# 4_Buck_Boost_12V.net
KiCad netlist of a schematic drawn in Altium Designer
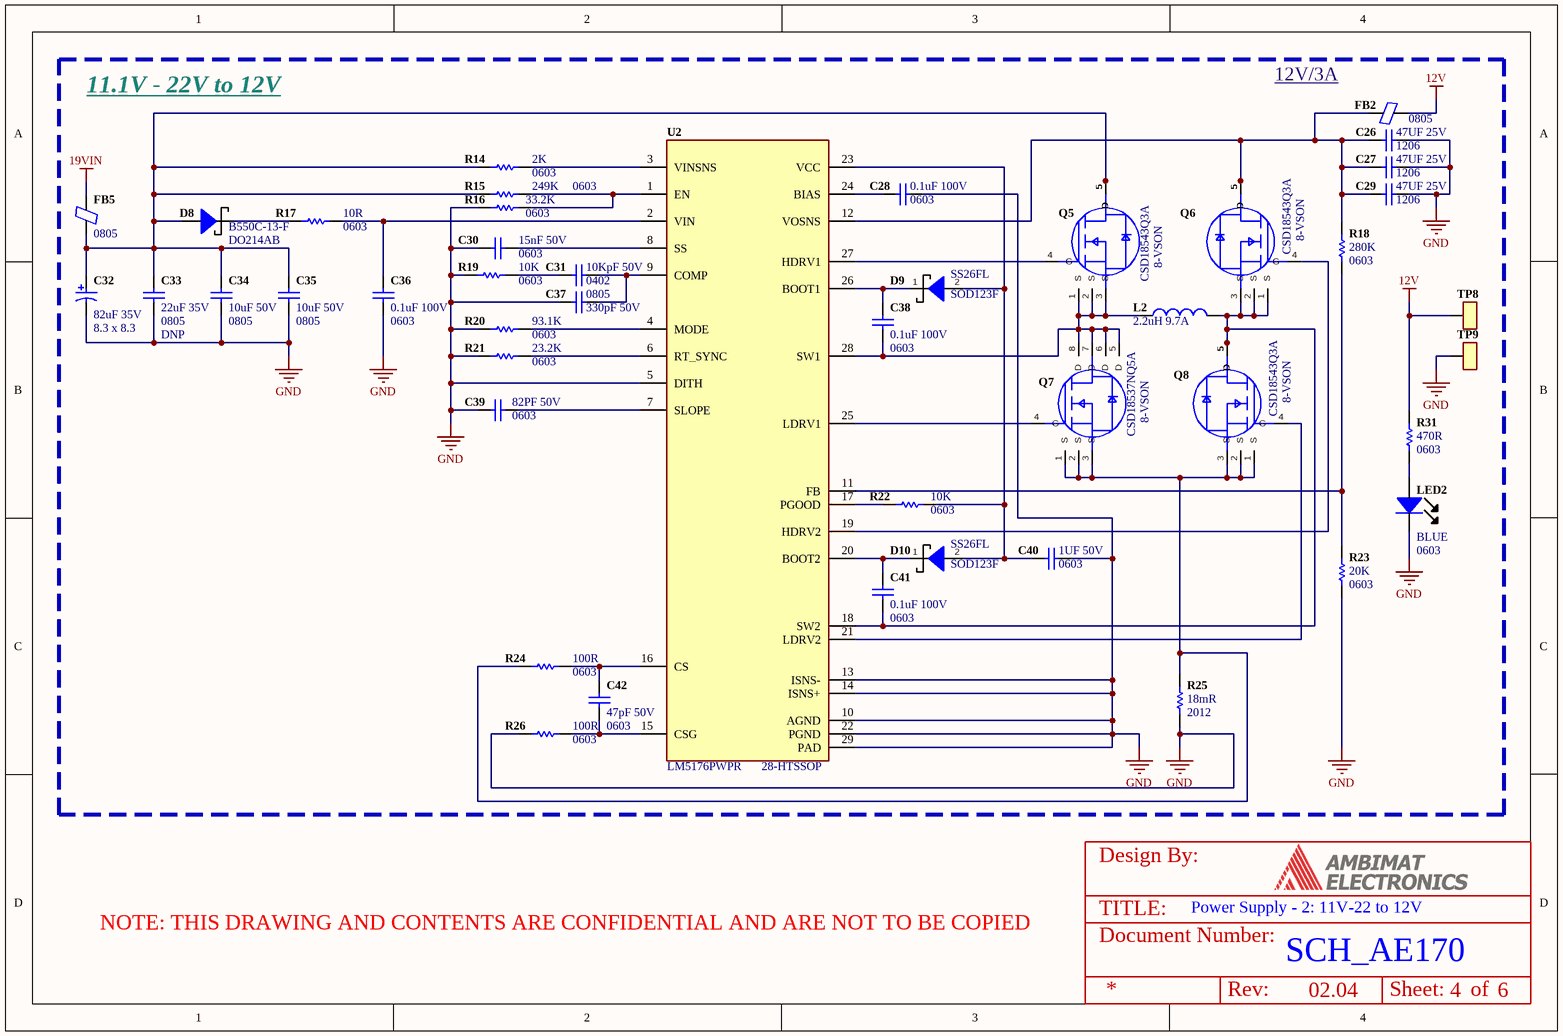
[diagram p0: 4. Buck Boost_12V.SchDoc]

(export (version "E")
  (design (tool "Eeschema 10.0.6"))
  (components
    (comp (ref "C26")
      (value "CAP CER 47UF 25V X5R 1206")
      (footprint "LimLabDL:1206 - NP")
      (fields
        (field (name "MANUFACTURER PART NUMBER") "C3216X5R1E476M160AC")
        (field (name "MANUFACTURER") "TDK Corporation")
        (field (name "VENDOR-1 PART NUMBER") "445-8047-1-ND")
        (field (name "PART NAME") "47UF 25V")
        (field (name "PCB FOOTPRINT") "1206")
      )
      (libsource (lib "LimLabDL") (part "CS47UF-25V1206"))
    )
    (comp (ref "C27")
      (value "CAP CER 47UF 25V X5R 1206")
      (footprint "LimLabDL:1206 - NP")
      (fields
        (field (name "MANUFACTURER PART NUMBER") "C3216X5R1E476M160AC")
        (field (name "MANUFACTURER") "TDK Corporation")
        (field (name "VENDOR-1 PART NUMBER") "445-8047-1-ND")
        (field (name "PART NAME") "47UF 25V")
        (field (name "PCB FOOTPRINT") "1206")
      )
      (libsource (lib "LimLabDL") (part "CS47UF-25V1206"))
    )
    (comp (ref "C28")
      (value "CAP CER 0.1UF 100V X7R 0603")
      (footprint "LimLabDL:0603C")
      (fields
        (field (name "MANU PART NUMBER") "CC0603KRX7R0BB104")
        (field (name "MANUFACTURER") "YAGEO")
        (field (name "PART NAME") "0.1uF 100V")
        (field (name "PCB FOOTPRINT") "0603")
        (field (name "VENDOR-1 PART NUMBER") "311-1523-1-ND")
      )
      (libsource (lib "LimLabDL") (part "CS0.1uF-100V0603"))
    )
    (comp (ref "C29")
      (value "CAP CER 47UF 25V X5R 1206")
      (footprint "LimLabDL:1206 - NP")
      (fields
        (field (name "MANUFACTURER PART NUMBER") "C3216X5R1E476M160AC")
        (field (name "MANUFACTURER") "TDK Corporation")
        (field (name "VENDOR-1 PART NUMBER") "445-8047-1-ND")
        (field (name "PART NAME") "47UF 25V")
        (field (name "PCB FOOTPRINT") "1206")
      )
      (libsource (lib "LimLabDL") (part "CS47UF-25V1206"))
    )
    (comp (ref "C30")
      (value "CAP CER 0.015UF 50V X7R 0603")
      (footprint "LimLabDL:0603C")
      (fields
        (field (name "MANUFACTURER PART NUMBER") "CL10B153KB8NNNC")
        (field (name "MANUFACTURER") "Samsung Electro-Mechanics")
        (field (name "VENDOR-1 PART NUMBER") "1276-1277-1-ND")
        (field (name "PART NAME") "15nF 50V")
        (field (name "PCB FOOTPRINT") "0603")
      )
      (libsource (lib "LimLabDL") (part "CS15nF-50V0603"))
    )
    (comp (ref "C31")
      (value "CAP CER 10000PF 50V X7R 0402")
      (footprint "LimLabDL:0402C")
      (fields
        (field (name "MANUFACTURER") "TDK Corporation")
        (field (name "VENDOR-1 PART NUMBER") "445-6893-1-ND")
        (field (name "PART NAME") "10KpF 50V")
        (field (name "PCB FOOTPRINT") "0402")
        (field (name "MANUFACTURER PART NUMBER") "CGA2B3X7R1H103K050BB")
      )
      (libsource (lib "LimLabDL") (part "CS10000pF-50V0402"))
    )
    (comp (ref "C32")
      (value "CAP ALUM POLY 82UF 20% 35V SMD")
      (footprint "LimLabDL:CAP_PC_8X12_NCH")
      (fields
        (field (name "MANU PART NUMBER") "35SVPF82M")
        (field (name "MANUFACTURER") "Panasonic")
        (field (name "VENDOR-1 PART NUMBER") "P16562CT-ND")
        (field (name "PART NAME") "82uF 35V")
        (field (name "PCB FOOTPRINT") "8.3 x 8.3")
      )
      (libsource (lib "LimLabDL") (part "CS82uF-35VALUM"))
    )
    (comp (ref "C33")
      (value "CAP CER 22UF 35V X5R 0805")
      (footprint "LimLabDL:0805C")
      (fields
        (field (name "MANU PART NUMBER") "C2012X5R1V226M125AC")
        (field (name "MANUFACTURER") "TDK Corporation")
        (field (name "MOUNTING") "DNP")
        (field (name "VENDOR-1 PART NUMBER") "445-14428-1-ND")
        (field (name "PART NAME") "22uF 35V")
        (field (name "PCB FOOTPRINT") "0805")
      )
      (libsource (lib "LimLabDL") (part "CS22uF-35V0805"))
    )
    (comp (ref "C34")
      (value "CAP CER 10UF 50V X5R 0805")
      (footprint "LimLabDL:0805C")
      (fields
        (field (name "MANU PART NUMBER") "GRM21BR61H106KE43L")
        (field (name "MANUFACTURER") "Murata Electronics")
        (field (name "VENDOR-1 PART NUMBER") "490-18663-1-ND")
        (field (name "PART NAME") "10uF 50V")
        (field (name "PCB FOOTPRINT") "0805")
      )
      (libsource (lib "LimLabDL") (part "CS10uF-50V0805"))
    )
    (comp (ref "C35")
      (value "CAP CER 10UF 50V X5R 0805")
      (footprint "LimLabDL:0805C")
      (fields
        (field (name "MANU PART NUMBER") "GRM21BR61H106KE43L")
        (field (name "MANUFACTURER") "Murata Electronics")
        (field (name "VENDOR-1 PART NUMBER") "490-18663-1-ND")
        (field (name "PART NAME") "10uF 50V")
        (field (name "PCB FOOTPRINT") "0805")
      )
      (libsource (lib "LimLabDL") (part "CS10uF-50V0805"))
    )
    (comp (ref "C36")
      (value "CAP CER 0.1UF 100V X7R 0603")
      (footprint "LimLabDL:0603C")
      (fields
        (field (name "MANU PART NUMBER") "CC0603KRX7R0BB104")
        (field (name "MANUFACTURER") "YAGEO")
        (field (name "PART NAME") "0.1uF 100V")
        (field (name "PCB FOOTPRINT") "0603")
        (field (name "VENDOR-1 PART NUMBER") "311-1523-1-ND")
      )
      (libsource (lib "LimLabDL") (part "CS0.1uF-100V0603"))
    )
    (comp (ref "C37")
      (value "CAP CER 330PF 50V C0G/NPO 0805")
      (footprint "LimLabDL:0805C")
      (fields
        (field (name "MANUFACTURER") "YAGEO")
        (field (name "VENDOR-1 PART NUMBER") "311-1117-1-ND")
        (field (name "PART NAME") "330pF 50V")
        (field (name "PCB FOOTPRINT") "0805")
        (field (name "MANUFACTURER PART NUMBER") "CC0805JRNPO9BN331")
      )
      (libsource (lib "LimLabDL") (part "CS330pF-50V0805"))
    )
    (comp (ref "C38")
      (value "CAP CER 0.1UF 100V X7R 0603")
      (footprint "LimLabDL:0603C")
      (fields
        (field (name "MANU PART NUMBER") "CC0603KRX7R0BB104")
        (field (name "MANUFACTURER") "YAGEO")
        (field (name "PART NAME") "0.1uF 100V")
        (field (name "PCB FOOTPRINT") "0603")
        (field (name "VENDOR-1 PART NUMBER") "311-1523-1-ND")
      )
      (libsource (lib "LimLabDL") (part "CS0.1uF-100V0603"))
    )
    (comp (ref "C39")
      (value "CAP CER 82PF 50V C0G/NPO 0603")
      (footprint "LimLabDL:0603C")
      (fields
        (field (name "MANUFACTURER") "Yageo")
        (field (name "VENDOR-1 PART NUMBER") "311-1068-1-ND")
        (field (name "PART NAME") "82PF 50V")
        (field (name "PCB FOOTPRINT") "0603")
        (field (name "MANU PART NUMBER") "CC0603JRNPO9BN820")
      )
      (libsource (lib "LimLabDL") (part "CS82pF-50V0603"))
    )
    (comp (ref "C40")
      (value "CAP CER 1UF 50V X7R 0603")
      (footprint "LimLabDL:0603C")
      (fields
        (field (name "MANU PART NUMBER") "CC0603KRX7R9BB105")
        (field (name "MANUFACTURER") "Yageo")
        (field (name "PART NAME") "1UF 50V")
        (field (name "PCB FOOTPRINT") "0603")
        (field (name "VENDOR-1 PART NUMBER") "311-2082-1-ND")
      )
      (libsource (lib "LimLabDL") (part "CS1uF-50V0603"))
    )
    (comp (ref "C41")
      (value "CAP CER 0.1UF 100V X7R 0603")
      (footprint "LimLabDL:0603C")
      (fields
        (field (name "MANU PART NUMBER") "CC0603KRX7R0BB104")
        (field (name "MANUFACTURER") "YAGEO")
        (field (name "PART NAME") "0.1uF 100V")
        (field (name "PCB FOOTPRINT") "0603")
        (field (name "VENDOR-1 PART NUMBER") "311-1523-1-ND")
      )
      (libsource (lib "LimLabDL") (part "CS0.1uF-100V0603"))
    )
    (comp (ref "C42")
      (value "CAP CER 47PF 50V X7R 10% 0603")
      (footprint "LimLabDL:0603C")
      (fields
        (field (name "MANUFACTURER") "KEMET")
        (field (name "VENDOR-1 PART NUMBER") "399-16402-1-ND")
        (field (name "PART NAME") "47pF 50V")
        (field (name "PCB FOOTPRINT") "0603")
        (field (name "MANUFACTURER PART NUMBER") "C0603C470K5RAC7867")
      )
      (libsource (lib "LimLabDL") (part "CS47pF-50V0603"))
    )
    (comp (ref "D8")
      (value "DIODE SCHOTTKY 50V 5A SMC")
      (footprint "LimLabDL:DO-214AB-SHKY")
      (fields
        (field (name "MANU PART NUMBER") "B550C-13-F")
        (field (name "MANUFACTURER") "Diodes Incorporated")
        (field (name "VENDOR-1 PART NUMBER") "B550C-FDICT-ND")
        (field (name "PCB FOOTPRINT") "DO214AB")
        (field (name "PART NAME") "B550C-13-F")
      )
      (libsource (lib "LimLabDL") (part "DS-B550C-13-F"))
    )
    (comp (ref "D9")
      (value "DIODE SCHOTTKY 60V 2A SOD123F")
      (footprint "LimLabDL:SOD123F-SHKY")
      (fields
        (field (name "MANU PART NUMBER") "SS26FL")
        (field (name "MANUFACTURER") "onsemi")
        (field (name "VENDOR-1 PART NUMBER") "SS26FLCT-ND")
        (field (name "PCB FOOTPRINT") "SOD123F")
        (field (name "PART NAME") "SS26FL")
      )
      (libsource (lib "LimLabDL") (part "DS-SS26FL"))
    )
    (comp (ref "D10")
      (value "DIODE SCHOTTKY 60V 2A SOD123F")
      (footprint "LimLabDL:SOD123F-SHKY")
      (fields
        (field (name "MANU PART NUMBER") "SS26FL")
        (field (name "MANUFACTURER") "onsemi")
        (field (name "VENDOR-1 PART NUMBER") "SS26FLCT-ND")
        (field (name "PCB FOOTPRINT") "SOD123F")
        (field (name "PART NAME") "SS26FL")
      )
      (libsource (lib "LimLabDL") (part "DS-SS26FL"))
    )
    (comp (ref "FB2")
      (value "FERRITE BEAD 120 OHM 0805 1LN")
      (footprint "LimLabDL:0805F")
      (fields
        (field (name "MANUFACTURER") "Pulse Electronics")
        (field (name "MANUFACTURER PART NUMBER") "ABUP00201209121Y00")
        (field (name "VENDOR-1 PART NUMBER") "553-ABUP00201209121Y00CT-ND")
        (field (name "PCB FOOTPRINT") "0805")
      )
      (libsource (lib "LimLabDL") (part "FB120OHM-0805"))
    )
    (comp (ref "FB5")
      (value "FERRITE BEAD 120 OHM 0805 1LN")
      (footprint "LimLabDL:0805F")
      (fields
        (field (name "MANUFACTURER") "Pulse Electronics")
        (field (name "MANUFACTURER PART NUMBER") "ABUP00201209121Y00")
        (field (name "VENDOR-1 PART NUMBER") "553-ABUP00201209121Y00CT-ND")
        (field (name "PCB FOOTPRINT") "0805")
      )
      (libsource (lib "LimLabDL") (part "FB120OHM-0805"))
    )
    (comp (ref "L2")
      (value "FIXED IND 2.2UH 9.7A 14.5MOHM SM")
      (footprint "LimLabDL:IND_BOURNS_SRP5030")
      (fields
        (field (name "MANUFACTURER PART NUMBER") "SRP5030CA-2R2M")
        (field (name "MANUFACTURER") "Bourns Inc.")
        (field (name "VENDOR-1 PART NUMBER") "SRP5030CA-2R2MCT-ND")
        (field (name "PART NAME") "2.2uH 9.7A")
      )
      (libsource (lib "LimLabDL") (part "LS2.2uH9.7A-5553"))
    )
    (comp (ref "LED2")
      (value "LB Q39G-L2N2-35-1")
      (footprint "LimLabDL:LED0603_BLUE")
      (description "LED BLUE CLEAR 3MM 470NM")
      (fields
        (field (name "MANUFACTURER") "OSRAM Opto Semiconductors Inc")
        (field (name "VENDOR-1 PART NUMBER") "475-2816-1-ND")
        (field (name "PCB FOOTPRINT") "0603")
        (field (name "COLOR") "BLUE")
      )
      (libsource (lib "LimLabDL") (part "LED-BLUE0603"))
    )
    (comp (ref "Q5")
      (value "MOSFET N-CH 60V 60A 8VSON")
      (footprint "LimLabDL:SON65P300X350X90-9N")
      (fields
        (field (name "MANU PART NUMBER") "CSD18543Q3A")
        (field (name "MANUFACTURER") "Texas Instruments")
        (field (name "VENDOR-1 PART NUMBER") "296-47321-1-ND")
        (field (name "PCB FOOTPRINT") "8-VSON")
        (field (name "PART NAME") "CSD18543Q3A")
      )
      (libsource (lib "LimLabDL") (part "MS-CSD18543Q3A"))
    )
    (comp (ref "Q6")
      (value "MOSFET N-CH 60V 60A 8VSON")
      (footprint "LimLabDL:SON65P300X350X90-9N")
      (fields
        (field (name "MANU PART NUMBER") "CSD18543Q3A")
        (field (name "MANUFACTURER") "Texas Instruments")
        (field (name "VENDOR-1 PART NUMBER") "296-47321-1-ND")
        (field (name "PCB FOOTPRINT") "8-VSON")
        (field (name "PART NAME") "CSD18543Q3A")
      )
      (libsource (lib "LimLabDL") (part "MS-CSD18543Q3A"))
    )
    (comp (ref "Q7")
      (value "MOSFET N-CH 60V 50A 8VSON")
      (footprint "LimLabDL:SON127P500X600")
      (fields
        (field (name "MANU PART NUMBER") "CSD18537NQ5A")
        (field (name "MANUFACTURER") "Texas Instruments")
        (field (name "VENDOR-1 PART NUMBER") "296-36455-1-ND")
        (field (name "PCB FOOTPRINT") "8-VSON")
        (field (name "PART NAME") "CSD18537NQ5A")
      )
      (libsource (lib "LimLabDL") (part "MS-CSD18537NQ5A"))
    )
    (comp (ref "Q8")
      (value "MOSFET N-CH 60V 60A 8VSON")
      (footprint "LimLabDL:SON65P300X350X90-9N")
      (fields
        (field (name "MANU PART NUMBER") "CSD18543Q3A")
        (field (name "MANUFACTURER") "Texas Instruments")
        (field (name "VENDOR-1 PART NUMBER") "296-47321-1-ND")
        (field (name "PCB FOOTPRINT") "8-VSON")
        (field (name "PART NAME") "CSD18543Q3A")
      )
      (libsource (lib "LimLabDL") (part "MS-CSD18543Q3A"))
    )
    (comp (ref "R14")
      (value "RS2K-0.1W0603")
      (footprint "LimLabDL:0603")
      (description "RES SMD 2K OHM 5% 1/10W 0603")
      (fields
        (field (name "MANU PART NUMBER") "ERJ-3GEYJ202V")
        (field (name "MANUFACTURER") "Panasonic")
        (field (name "PART NAME") "2K")
        (field (name "PCB FOOTPRINT") "0603")
      )
      (libsource (lib "LimLabDL") (part "RS2K-0.1W0603"))
    )
    (comp (ref "R15")
      (value "RES SMD 249K OHM 1% 1/10W 0603")
      (footprint "LimLabDL:0603")
      (fields
        (field (name "MANUFACTURER PART NUMBER") "AC0603FR-07249KL")
        (field (name "MANUFACTURER") "Yageo")
        (field (name "VENDOR-1 PART NUMBER") "13-AC0603FR-07249KLCT-ND")
        (field (name "PART NAME") "249K")
        (field (name "PCB FOOTPRINT") "0603")
      )
      (libsource (lib "LimLabDL") (part "RS249K-0.1W0603"))
    )
    (comp (ref "R16")
      (value "RES SMD 33.2K OHM 1% 1/10W 0603")
      (footprint "LimLabDL:0603")
      (fields
        (field (name "MANUFACTURER") "Panasonic Electronic Components")
        (field (name "VENDOR-1 PART NUMBER") "P33.2KHCT-ND")
        (field (name "PART NAME") "33.2K")
        (field (name "PCB FOOTPRINT") "0603")
        (field (name "MANU PART NUMBER") "ERJ-3EKF3322V")
      )
      (libsource (lib "LimLabDL") (part "RS33.2K-0.1W0603"))
    )
    (comp (ref "R17")
      (value "RES SMD 10 OHM 1% 1/10W 0603")
      (footprint "LimLabDL:0603")
      (fields
        (field (name "MANU PART NUMBER") "CRCW060310R0FKEA")
        (field (name "MANUFACTURER") "Vishay Dale")
        (field (name "VENDOR-1 PART NUMBER") "541-10.0HCT-ND")
        (field (name "PART NAME") "10R")
        (field (name "PCB FOOTPRINT") "0603")
      )
      (libsource (lib "LimLabDL") (part "RS10R-0.1W0603"))
    )
    (comp (ref "R18")
      (value "RES SMD 280K OHM 1% 1/10W 0603")
      (footprint "LimLabDL:0603")
      (fields
        (field (name "MANU PART NUMBER") "CRCW0603280KFKEA")
        (field (name "MANUFACTURER") "Vishay Dale")
        (field (name "VENDOR-1 PART NUMBER") "541-280KHCT-ND")
        (field (name "PART NAME") "280K")
        (field (name "PCB FOOTPRINT") "0603")
      )
      (libsource (lib "LimLabDL") (part "RS280K-0.1W0603"))
    )
    (comp (ref "R19")
      (value "RES SMD 10K OHM 5% 1/10W 0603")
      (footprint "LimLabDL:0603")
      (fields
        (field (name "MANUFACTURER PART NUMBER") "RC0603JR-0710KL")
        (field (name "MANUFACTURER") "Yageo")
        (field (name "VENDOR-1 PART NUMBER") "311-10KGRCT-ND")
        (field (name "PART NAME") "10K")
        (field (name "PCB FOOTPRINT") "0603")
      )
      (libsource (lib "LimLabDL") (part "RS10K-0.1W0603"))
    )
    (comp (ref "R20")
      (value "RES 93.1K OHM 1% 1/10W 0603")
      (footprint "LimLabDL:0603")
      (fields
        (field (name "MANU PART NUMBER") "RC0603FR-0793K1L")
        (field (name "MANUFACTURER") "YAGEO")
        (field (name "VENDOR-1 PART NUMBER") "311-93.1KHRCT-ND")
        (field (name "PART NAME") "93.1K")
        (field (name "PCB FOOTPRINT") "0603")
      )
      (libsource (lib "LimLabDL") (part "RS93.1K-0.1W0603"))
    )
    (comp (ref "R21")
      (value "RES 23.2K OHM 1% 1/10W 0603")
      (footprint "LimLabDL:0603")
      (fields
        (field (name "MANU PART NUMBER") "RC0603FR-0723K2L")
        (field (name "MANUFACTURER") "YAGEO")
        (field (name "VENDOR-1 PART NUMBER") "311-23.2KHRCT-ND")
        (field (name "PART NAME") "23.2K")
        (field (name "PCB FOOTPRINT") "0603")
      )
      (libsource (lib "LimLabDL") (part "RS23.2K-0.1W0603"))
    )
    (comp (ref "R22")
      (value "RES SMD 10K OHM 5% 1/10W 0603")
      (footprint "LimLabDL:0603")
      (fields
        (field (name "MANUFACTURER") "Yageo")
        (field (name "VENDOR-1 PART NUMBER") "311-10KGRCT-ND")
        (field (name "PCB FOOTPRINT") "0603")
        (field (name "PART NAME") "10K")
        (field (name "MANUFACTURER PART NUMBER") "RC0603JR-0710KL")
      )
      (libsource (lib "LimLabDL") (part "RS10K-0.1W0603"))
    )
    (comp (ref "R23")
      (value "RES SMD 20K OHM 5% 1/10W 0603")
      (footprint "LimLabDL:0603")
      (fields
        (field (name "MANU PART NUMBER") "CRCW060320K0JNEA")
        (field (name "MANUFACTURER") "Vishay Dale")
        (field (name "VENDOR-1 PART NUMBER") "541-20KGCT-ND")
        (field (name "PCB FOOTPRINT") "0603")
        (field (name "PART NAME") "20K")
      )
      (libsource (lib "LimLabDL") (part "RS20K-0.1W0603"))
    )
    (comp (ref "R24")
      (value "RES SMD 100 OHM 1% 1/10W 0603")
      (footprint "LimLabDL:0603")
      (fields
        (field (name "MANU PART NUMBER") "CRCW0603100RFKEA")
        (field (name "MANUFACTURER") "Vishay Dale")
        (field (name "VENDOR-1 PART NUMBER") "541-100HCT-ND")
        (field (name "PCB FOOTPRINT") "0603")
        (field (name "PART NAME") "100R")
      )
      (libsource (lib "LimLabDL") (part "RS100R-0.1W0603"))
    )
    (comp (ref "R25")
      (value "RES 0.018 OHM 1W 1206 WIDE")
      (footprint "LimLabDL:1206_W")
      (fields
        (field (name "MANU PART NUMBER") "PRL1632-R018-F-T1")
        (field (name "MANUFACTURER") "Susumu")
        (field (name "VENDOR-1 PART NUMBER") "PRL1632.018FCT-ND")
        (field (name "PART NAME") "18mR")
        (field (name "PCB FOOTPRINT") "2012")
      )
      (libsource (lib "LimLabDL") (part "RS18mR-1W1206"))
    )
    (comp (ref "R26")
      (value "RES SMD 100 OHM 1% 1/10W 0603")
      (footprint "LimLabDL:0603")
      (fields
        (field (name "MANU PART NUMBER") "CRCW0603100RFKEA")
        (field (name "MANUFACTURER") "Vishay Dale")
        (field (name "VENDOR-1 PART NUMBER") "541-100HCT-ND")
        (field (name "PCB FOOTPRINT") "0603")
        (field (name "PART NAME") "100R")
      )
      (libsource (lib "LimLabDL") (part "RS100R-0.1W0603"))
    )
    (comp (ref "R31")
      (value "RES 470 OHM 1/10W 5% 0603 SMD")
      (footprint "LimLabDL:0603")
      (fields
        (field (name "MANU PART NUMBER") "RC0603JR-07470RL")
        (field (name "MANUFACTURER") "YAGEO")
        (field (name "VENDOR-1 PART NUMBER") "311-470GRCT-ND")
        (field (name "PART NAME") "470R")
        (field (name "PCB FOOTPRINT") "0603")
      )
      (libsource (lib "LimLabDL") (part "RS470R-1/10W0603"))
    )
    (comp (ref "TP8")
      (value "TEST POINT")
      (footprint "LimLabDL:TP-1.5mmSMD")
      (description "SMD TEST POINT")
      (libsource (lib "LimLabDL") (part "TP-1.5mmSMD"))
    )
    (comp (ref "TP9")
      (value "TEST POINT")
      (footprint "LimLabDL:TP-1.5mmSMD")
      (description "SMD TEST POINT")
      (libsource (lib "LimLabDL") (part "TP-1.5mmSMD"))
    )
    (comp (ref "U2")
      (value "LM5176PWPR")
      (footprint "LimLabDL:HSSOP-28")
      (fields
        (field (name "MANUFACTURER") "Texas Instruments")
        (field (name "VENDOR-1 PART NUMBER") "296-49223-1-ND")
        (field (name "MANUFACTURER PART NUMBE") "LM5176PWPR")
        (field (name "PCB FOOTPRINT") "28-HTSSOP")
      )
      (libsource (lib "LimLabDL") (part "IC28P-LM5176PWPR"))
    )
  )
  (nets
    (net (code "1") (name "12V") (class "Default")
      (node (ref "FB2") (pin "2") (pinfunction "2_2") (pintype "passive"))
      (node (ref "R31") (pin "2") (pinfunction "2_2") (pintype "passive"))
      (node (ref "TP8") (pin "1") (pinfunction "1_1") (pintype "passive"))
    )
    (net (code "2") (name "19VIN") (class "Default")
      (node (ref "FB5") (pin "1") (pinfunction "1_1") (pintype "passive"))
    )
    (net (code "3") (name "GND") (class "Default")
      (node (ref "C26") (pin "2") (pinfunction "2_2") (pintype "passive"))
      (node (ref "C27") (pin "2") (pinfunction "2_2") (pintype "passive"))
      (node (ref "C28") (pin "2") (pinfunction "2_2") (pintype "passive"))
      (node (ref "C29") (pin "2") (pinfunction "2_2") (pintype "passive"))
      (node (ref "C30") (pin "1") (pinfunction "1_1") (pintype "passive"))
      (node (ref "C32") (pin "2") (pinfunction "2_2") (pintype "passive"))
      (node (ref "C33") (pin "2") (pinfunction "2_2") (pintype "passive"))
      (node (ref "C34") (pin "2") (pinfunction "2_2") (pintype "passive"))
      (node (ref "C35") (pin "2") (pinfunction "2_2") (pintype "passive"))
      (node (ref "C36") (pin "2") (pinfunction "2_2") (pintype "passive"))
      (node (ref "C37") (pin "1") (pinfunction "1_1") (pintype "passive"))
      (node (ref "C39") (pin "1") (pinfunction "1_1") (pintype "passive"))
      (node (ref "C40") (pin "2") (pinfunction "2_2") (pintype "passive"))
      (node (ref "LED2") (pin "2") (pinfunction "K_2") (pintype "passive"))
      (node (ref "R16") (pin "1") (pinfunction "1_1") (pintype "passive"))
      (node (ref "R19") (pin "1") (pinfunction "1_1") (pintype "passive"))
      (node (ref "R20") (pin "1") (pinfunction "1_1") (pintype "passive"))
      (node (ref "R21") (pin "1") (pinfunction "1_1") (pintype "passive"))
      (node (ref "R23") (pin "1") (pinfunction "1_1") (pintype "passive"))
      (node (ref "R25") (pin "1") (pinfunction "1_1") (pintype "passive"))
      (node (ref "R26") (pin "1") (pinfunction "1_1") (pintype "passive"))
      (node (ref "TP9") (pin "1") (pinfunction "1_1") (pintype "passive"))
      (node (ref "U2") (pin "10") (pinfunction "AGND_10") (pintype "passive"))
      (node (ref "U2") (pin "13") (pinfunction "ISNS-_13") (pintype "passive"))
      (node (ref "U2") (pin "14") (pinfunction "ISNS+_14") (pintype "passive"))
      (node (ref "U2") (pin "22") (pinfunction "PGND_22") (pintype "passive"))
      (node (ref "U2") (pin "29") (pinfunction "PAD_29") (pintype "passive"))
      (node (ref "U2") (pin "5") (pinfunction "DITH_5") (pintype "passive"))
    )
    (net (code "4") (name "Net-(C31-Pad1)") (class "Default")
      (node (ref "C31") (pin "1") (pinfunction "1_1") (pintype "passive"))
      (node (ref "R19") (pin "2") (pinfunction "2_2") (pintype "passive"))
    )
    (net (code "5") (name "Net-(D8-Pad1)") (class "Default")
      (node (ref "D8") (pin "1") (pinfunction "1_1") (pintype "passive"))
      (node (ref "R17") (pin "1") (pinfunction "1_1") (pintype "passive"))
    )
    (net (code "6") (name "Net-(LED2-A)") (class "Default")
      (node (ref "LED2") (pin "1") (pinfunction "A_1") (pintype "passive"))
      (node (ref "R31") (pin "1") (pinfunction "1_1") (pintype "passive"))
    )
    (net (code "7") (name "Net-(Q5-D)") (class "Default")
      (node (ref "C32") (pin "1") (pinfunction "1_1") (pintype "passive"))
      (node (ref "C33") (pin "1") (pinfunction "1_1") (pintype "passive"))
      (node (ref "C34") (pin "1") (pinfunction "1_1") (pintype "passive"))
      (node (ref "C35") (pin "1") (pinfunction "1_1") (pintype "passive"))
      (node (ref "D8") (pin "2") (pinfunction "2_2") (pintype "passive"))
      (node (ref "FB5") (pin "2") (pinfunction "2_2") (pintype "passive"))
      (node (ref "Q5") (pin "5") (pinfunction "D_5") (pintype "passive"))
      (node (ref "R14") (pin "1") (pinfunction "1_1") (pintype "passive"))
      (node (ref "R15") (pin "1") (pinfunction "1_1") (pintype "passive"))
    )
    (net (code "8") (name "Net-(Q5-G)") (class "Default")
      (node (ref "Q5") (pin "4") (pinfunction "G_4") (pintype "passive"))
      (node (ref "U2") (pin "27") (pinfunction "HDRV1_27") (pintype "passive"))
    )
    (net (code "9") (name "Net-(Q6-D)") (class "Default")
      (node (ref "C26") (pin "1") (pinfunction "1_1") (pintype "passive"))
      (node (ref "C27") (pin "1") (pinfunction "1_1") (pintype "passive"))
      (node (ref "C29") (pin "1") (pinfunction "1_1") (pintype "passive"))
      (node (ref "FB2") (pin "1") (pinfunction "1_1") (pintype "passive"))
      (node (ref "Q6") (pin "5") (pinfunction "D_5") (pintype "passive"))
      (node (ref "R18") (pin "2") (pinfunction "2_2") (pintype "passive"))
      (node (ref "U2") (pin "12") (pinfunction "VOSNS_12") (pintype "passive"))
    )
    (net (code "10") (name "Net-(Q6-G)") (class "Default")
      (node (ref "Q6") (pin "4") (pinfunction "G_4") (pintype "passive"))
      (node (ref "U2") (pin "19") (pinfunction "HDRV2_19") (pintype "passive"))
    )
    (net (code "11") (name "Net-(Q7-G)") (class "Default")
      (node (ref "Q7") (pin "4") (pinfunction "G_4") (pintype "passive"))
      (node (ref "U2") (pin "25") (pinfunction "LDRV1_25") (pintype "passive"))
    )
    (net (code "12") (name "Net-(Q7-S-Pad1)") (class "Default")
      (node (ref "Q7") (pin "1") (pinfunction "S_1") (pintype "passive"))
      (node (ref "Q7") (pin "2") (pinfunction "S_2") (pintype "passive"))
      (node (ref "Q7") (pin "3") (pinfunction "S_3") (pintype "passive"))
      (node (ref "Q8") (pin "1") (pinfunction "S_1") (pintype "passive"))
      (node (ref "Q8") (pin "2") (pinfunction "S_2") (pintype "passive"))
      (node (ref "Q8") (pin "3") (pinfunction "S_3") (pintype "passive"))
      (node (ref "R24") (pin "1") (pinfunction "1_1") (pintype "passive"))
      (node (ref "R25") (pin "2") (pinfunction "2_2") (pintype "passive"))
    )
    (net (code "13") (name "Net-(Q8-D)") (class "Default")
      (node (ref "C41") (pin "1") (pinfunction "1_1") (pintype "passive"))
      (node (ref "L2") (pin "2") (pinfunction "2_2") (pintype "passive"))
      (node (ref "Q6") (pin "1") (pinfunction "S_1") (pintype "passive"))
      (node (ref "Q6") (pin "2") (pinfunction "S_2") (pintype "passive"))
      (node (ref "Q6") (pin "3") (pinfunction "S_3") (pintype "passive"))
      (node (ref "Q8") (pin "5") (pinfunction "D_5") (pintype "passive"))
      (node (ref "U2") (pin "18") (pinfunction "SW2_18") (pintype "passive"))
    )
    (net (code "14") (name "Net-(Q8-G)") (class "Default")
      (node (ref "Q8") (pin "4") (pinfunction "G_4") (pintype "passive"))
      (node (ref "U2") (pin "21") (pinfunction "LDRV2_21") (pintype "passive"))
    )
    (net (code "15") (name "Net-(U2-BIAS)") (class "Default")
      (node (ref "C28") (pin "1") (pinfunction "1_1") (pintype "passive"))
      (node (ref "U2") (pin "24") (pinfunction "BIAS_24") (pintype "passive"))
    )
    (net (code "16") (name "Net-(U2-BOOT1)") (class "Default")
      (node (ref "C38") (pin "2") (pinfunction "2_2") (pintype "passive"))
      (node (ref "D9") (pin "1") (pinfunction "1_1") (pintype "passive"))
      (node (ref "U2") (pin "26") (pinfunction "BOOT1_26") (pintype "passive"))
    )
    (net (code "17") (name "Net-(U2-BOOT2)") (class "Default")
      (node (ref "C41") (pin "2") (pinfunction "2_2") (pintype "passive"))
      (node (ref "D10") (pin "1") (pinfunction "1_1") (pintype "passive"))
      (node (ref "U2") (pin "20") (pinfunction "BOOT2_20") (pintype "passive"))
    )
    (net (code "18") (name "Net-(U2-COMP)") (class "Default")
      (node (ref "C31") (pin "2") (pinfunction "2_2") (pintype "passive"))
      (node (ref "C37") (pin "2") (pinfunction "2_2") (pintype "passive"))
      (node (ref "U2") (pin "9") (pinfunction "COMP_9") (pintype "passive"))
    )
    (net (code "19") (name "Net-(U2-CS)") (class "Default")
      (node (ref "C42") (pin "1") (pinfunction "1_1") (pintype "passive"))
      (node (ref "R24") (pin "2") (pinfunction "2_2") (pintype "passive"))
      (node (ref "U2") (pin "16") (pinfunction "CS_16") (pintype "passive"))
    )
    (net (code "20") (name "Net-(U2-CSG)") (class "Default")
      (node (ref "C42") (pin "2") (pinfunction "2_2") (pintype "passive"))
      (node (ref "R26") (pin "2") (pinfunction "2_2") (pintype "passive"))
      (node (ref "U2") (pin "15") (pinfunction "CSG_15") (pintype "passive"))
    )
    (net (code "21") (name "Net-(U2-EN)") (class "Default")
      (node (ref "R15") (pin "2") (pinfunction "2_2") (pintype "passive"))
      (node (ref "R16") (pin "2") (pinfunction "2_2") (pintype "passive"))
      (node (ref "U2") (pin "1") (pinfunction "EN_1") (pintype "passive"))
    )
    (net (code "22") (name "Net-(U2-FB)") (class "Default")
      (node (ref "R18") (pin "1") (pinfunction "1_1") (pintype "passive"))
      (node (ref "R23") (pin "2") (pinfunction "2_2") (pintype "passive"))
      (node (ref "U2") (pin "11") (pinfunction "FB_11") (pintype "passive"))
    )
    (net (code "23") (name "Net-(U2-MODE)") (class "Default")
      (node (ref "R20") (pin "2") (pinfunction "2_2") (pintype "passive"))
      (node (ref "U2") (pin "4") (pinfunction "MODE_4") (pintype "passive"))
    )
    (net (code "24") (name "Net-(U2-PGOOD)") (class "Default")
      (node (ref "R22") (pin "1") (pinfunction "1_1") (pintype "passive"))
      (node (ref "U2") (pin "17") (pinfunction "PGOOD_17") (pintype "passive"))
    )
    (net (code "25") (name "Net-(U2-RT_SYNC)") (class "Default")
      (node (ref "R21") (pin "2") (pinfunction "2_2") (pintype "passive"))
      (node (ref "U2") (pin "6") (pinfunction "RT_SYNC_6") (pintype "passive"))
    )
    (net (code "26") (name "Net-(U2-SLOPE)") (class "Default")
      (node (ref "C39") (pin "2") (pinfunction "2_2") (pintype "passive"))
      (node (ref "U2") (pin "7") (pinfunction "SLOPE_7") (pintype "passive"))
    )
    (net (code "27") (name "Net-(U2-SS)") (class "Default")
      (node (ref "C30") (pin "2") (pinfunction "2_2") (pintype "passive"))
      (node (ref "U2") (pin "8") (pinfunction "SS_8") (pintype "passive"))
    )
    (net (code "28") (name "Net-(U2-SW1)") (class "Default")
      (node (ref "C38") (pin "1") (pinfunction "1_1") (pintype "passive"))
      (node (ref "L2") (pin "1") (pinfunction "1_1") (pintype "passive"))
      (node (ref "Q5") (pin "1") (pinfunction "S_1") (pintype "passive"))
      (node (ref "Q5") (pin "2") (pinfunction "S_2") (pintype "passive"))
      (node (ref "Q5") (pin "3") (pinfunction "S_3") (pintype "passive"))
      (node (ref "Q7") (pin "5") (pinfunction "D_5") (pintype "passive"))
      (node (ref "Q7") (pin "6") (pinfunction "D_6") (pintype "passive"))
      (node (ref "Q7") (pin "7") (pinfunction "D_7") (pintype "passive"))
      (node (ref "Q7") (pin "8") (pinfunction "D_8") (pintype "passive"))
      (node (ref "U2") (pin "28") (pinfunction "SW1_28") (pintype "passive"))
    )
    (net (code "29") (name "Net-(U2-VCC)") (class "Default")
      (node (ref "C40") (pin "1") (pinfunction "1_1") (pintype "passive"))
      (node (ref "D10") (pin "2") (pinfunction "2_2") (pintype "passive"))
      (node (ref "D9") (pin "2") (pinfunction "2_2") (pintype "passive"))
      (node (ref "R22") (pin "2") (pinfunction "2_2") (pintype "passive"))
      (node (ref "U2") (pin "23") (pinfunction "VCC_23") (pintype "passive"))
    )
    (net (code "30") (name "Net-(U2-VIN)") (class "Default")
      (node (ref "C36") (pin "1") (pinfunction "1_1") (pintype "passive"))
      (node (ref "R17") (pin "2") (pinfunction "2_2") (pintype "passive"))
      (node (ref "U2") (pin "2") (pinfunction "VIN_2") (pintype "passive"))
    )
    (net (code "31") (name "Net-(U2-VINSNS)") (class "Default")
      (node (ref "R14") (pin "2") (pinfunction "2_2") (pintype "passive"))
      (node (ref "U2") (pin "3") (pinfunction "VINSNS_3") (pintype "passive"))
    )
  )
)
